# psu-12v.net
KiCad netlist of a schematic drawn in EAGLE
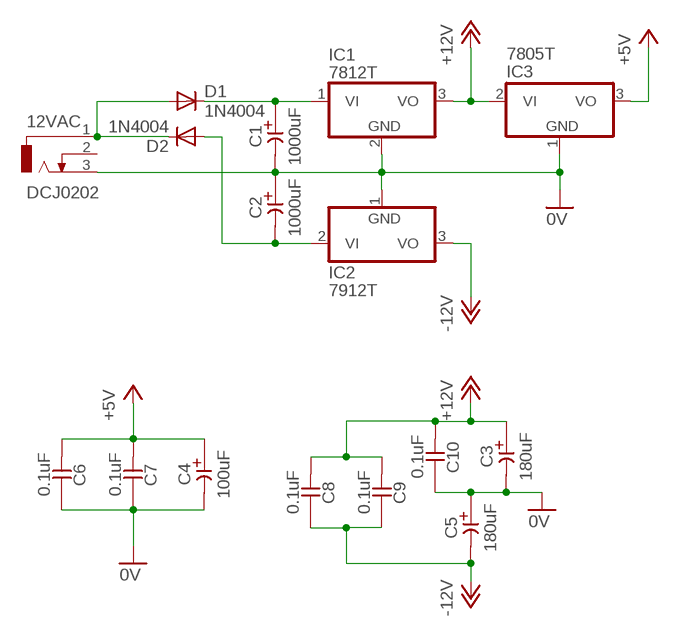
[diagram p0: schematic, sheet 1]

(export (version "E")
  (design (tool "Eeschema 10.0.6"))
  (components
    (comp (ref "12VAC")
      (value "DCJ0202")
      (footprint "eagle-import:DCJ0202")
      (libsource (lib "eagle-import") (part "DCJ0202"))
    )
    (comp (ref "C1")
      (value "1000uF")
      (footprint "eagle-import:E5-8,5")
      (libsource (lib "eagle-import") (part "CE-USE5-8.5"))
    )
    (comp (ref "C2")
      (value "1000uF")
      (footprint "eagle-import:E5-8,5")
      (libsource (lib "eagle-import") (part "CE-USE5-8.5"))
    )
    (comp (ref "C3")
      (value "180uF")
      (footprint "eagle-import:E5-8,5")
      (libsource (lib "eagle-import") (part "CE-USE5-8.5"))
    )
    (comp (ref "C4")
      (value "100uF")
      (footprint "eagle-import:E5-8,5")
      (libsource (lib "eagle-import") (part "CE-USE5-8.5"))
    )
    (comp (ref "C5")
      (value "180uF")
      (footprint "eagle-import:E5-8,5")
      (libsource (lib "eagle-import") (part "CE-USE5-8.5"))
    )
    (comp (ref "C6")
      (value "0.1uF")
      (footprint "eagle-import:C050-024X044")
      (libsource (lib "eagle-import") (part "CC-US050-024X044"))
    )
    (comp (ref "C7")
      (value "0.1uF")
      (footprint "eagle-import:C050-024X044")
      (libsource (lib "eagle-import") (part "CC-US050-024X044"))
    )
    (comp (ref "C8")
      (value "0.1uF")
      (footprint "eagle-import:C050-024X044")
      (libsource (lib "eagle-import") (part "CC-US050-024X044"))
    )
    (comp (ref "C9")
      (value "0.1uF")
      (footprint "eagle-import:C050-024X044")
      (libsource (lib "eagle-import") (part "CC-US050-024X044"))
    )
    (comp (ref "C10")
      (value "0.1uF")
      (footprint "eagle-import:C050-024X044")
      (libsource (lib "eagle-import") (part "CC-US050-024X044"))
    )
    (comp (ref "D1")
      (value "1N4004")
      (footprint "eagle-import:DO41-10")
      (libsource (lib "eagle-import") (part "1N4004"))
    )
    (comp (ref "D2")
      (value "1N4004")
      (footprint "eagle-import:DO41-10")
      (libsource (lib "eagle-import") (part "1N4004"))
    )
    (comp (ref "IC1")
      (value "7812T")
      (footprint "eagle-import:TO220H")
      (libsource (lib "eagle-import") (part "78T12"))
    )
    (comp (ref "IC2")
      (value "7912T")
      (footprint "eagle-import:TO220H")
      (libsource (lib "eagle-import") (part "79T12"))
    )
    (comp (ref "IC3")
      (value "7805T")
      (footprint "eagle-import:TO220H")
      (libsource (lib "eagle-import") (part "79T05"))
    )
  )
  (nets
    (net (code "1") (name "+5V") (class "Default")
      (node (ref "C4") (pin "+") (pinfunction "+_+") (pintype "passive"))
      (node (ref "C6") (pin "2") (pinfunction "2_2") (pintype "passive"))
      (node (ref "C7") (pin "2") (pinfunction "2_2") (pintype "passive"))
      (node (ref "IC3") (pin "3") (pinfunction "VO_3") (pintype "passive"))
    )
    (net (code "2") (name "+12V") (class "Default")
      (node (ref "C10") (pin "2") (pinfunction "2_2") (pintype "passive"))
      (node (ref "C3") (pin "+") (pinfunction "+_+") (pintype "passive"))
      (node (ref "C8") (pin "2") (pinfunction "2_2") (pintype "passive"))
      (node (ref "C9") (pin "2") (pinfunction "2_2") (pintype "passive"))
      (node (ref "IC1") (pin "3") (pinfunction "VO_3") (pintype "passive"))
      (node (ref "IC3") (pin "2") (pinfunction "VI_2") (pintype "input"))
    )
    (net (code "3") (name "-12V") (class "Default")
      (node (ref "C5") (pin "-") (pinfunction "-_-") (pintype "passive"))
      (node (ref "C8") (pin "1") (pinfunction "1_1") (pintype "passive"))
      (node (ref "C9") (pin "1") (pinfunction "1_1") (pintype "passive"))
      (node (ref "IC2") (pin "3") (pinfunction "VO_3") (pintype "passive"))
    )
    (net (code "4") (name "0V") (class "Default")
      (node (ref "12VAC") (pin "3") (pinfunction "3_3") (pintype "passive"))
      (node (ref "C1") (pin "-") (pinfunction "-_-") (pintype "passive"))
      (node (ref "C10") (pin "1") (pinfunction "1_1") (pintype "passive"))
      (node (ref "C2") (pin "+") (pinfunction "+_+") (pintype "passive"))
      (node (ref "C3") (pin "-") (pinfunction "-_-") (pintype "passive"))
      (node (ref "C4") (pin "-") (pinfunction "-_-") (pintype "passive"))
      (node (ref "C5") (pin "+") (pinfunction "+_+") (pintype "passive"))
      (node (ref "C6") (pin "1") (pinfunction "1_1") (pintype "passive"))
      (node (ref "C7") (pin "1") (pinfunction "1_1") (pintype "passive"))
      (node (ref "IC1") (pin "2") (pinfunction "GND_2") (pintype "passive"))
      (node (ref "IC2") (pin "1") (pinfunction "GND_1") (pintype "passive"))
      (node (ref "IC3") (pin "1") (pinfunction "GND_1") (pintype "passive"))
    )
    (net (code "5") (name "Net-(12VAC-Pad1)") (class "Default")
      (node (ref "12VAC") (pin "1") (pinfunction "1_1") (pintype "passive"))
      (node (ref "D1") (pin "A") (pinfunction "A_A") (pintype "passive"))
      (node (ref "D2") (pin "C") (pinfunction "C_C") (pintype "passive"))
    )
    (net (code "6") (name "Net-(IC1-VI)") (class "Default")
      (node (ref "C1") (pin "+") (pinfunction "+_+") (pintype "passive"))
      (node (ref "D1") (pin "C") (pinfunction "C_C") (pintype "passive"))
      (node (ref "IC1") (pin "1") (pinfunction "VI_1") (pintype "input"))
    )
    (net (code "7") (name "Net-(IC2-VI)") (class "Default")
      (node (ref "C2") (pin "-") (pinfunction "-_-") (pintype "passive"))
      (node (ref "D2") (pin "A") (pinfunction "A_A") (pintype "passive"))
      (node (ref "IC2") (pin "2") (pinfunction "VI_2") (pintype "input"))
    )
    (net (code "8") (name "unconnected-(12VAC-Pad2)") (class "Default")
      (node (ref "12VAC") (pin "2") (pinfunction "2_2") (pintype "passive"))
    )
  )
)
